# braino_schematic.net
KiCad netlist of a schematic drawn in EAGLE
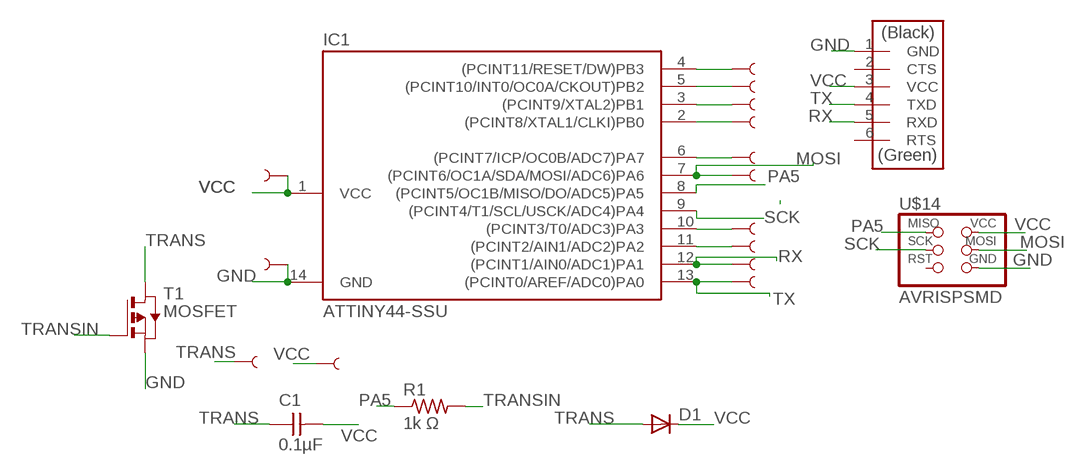
[diagram p0: schematic, sheet 1]

(export (version "E")
  (design (tool "Eeschema 10.0.6"))
  (components
    (comp (ref "C1")
      (value "0.1µF")
      (footprint "eagle-import:C1206FAB")
      (libsource (lib "eagle-import") (part "CAP-UNPOLARIZEDFAB"))
    )
    (comp (ref "D1")
      (value "DIODESOD123")
      (footprint "eagle-import:SOD123")
      (libsource (lib "eagle-import") (part "DIODESOD123"))
    )
    (comp (ref "IC1")
      (value "ATTINY44-SSU")
      (footprint "eagle-import:SOIC14")
      (libsource (lib "eagle-import") (part "ATTINY44-SSU"))
    )
    (comp (ref "R1")
      (value "1k Ω")
      (footprint "eagle-import:R1206FAB")
      (libsource (lib "eagle-import") (part "RES-US1206FAB"))
    )
    (comp (ref "T1")
      (value "MOSFET")
      (footprint "eagle-import:SOT-23")
      (libsource (lib "eagle-import") (part "PMOSFETSOT23"))
    )
    (comp (ref "U$1")
      (value "SEWTAP10")
      (footprint "eagle-import:PETAL-LONG-2-2SIDE")
      (libsource (lib "eagle-import") (part "SEWTAP10"))
    )
    (comp (ref "U$2")
      (value "SEWTAP10")
      (footprint "eagle-import:PETAL-LONG-2-2SIDE")
      (libsource (lib "eagle-import") (part "SEWTAP10"))
    )
    (comp (ref "U$3")
      (value "SEWTAP10")
      (footprint "eagle-import:PETAL-LONG-2-2SIDE")
      (libsource (lib "eagle-import") (part "SEWTAP10"))
    )
    (comp (ref "U$4")
      (value "SEWTAP10")
      (footprint "eagle-import:PETAL-LONG-2-2SIDE")
      (libsource (lib "eagle-import") (part "SEWTAP10"))
    )
    (comp (ref "U$5")
      (value "SEWTAP10")
      (footprint "eagle-import:PETAL-LONG-2-2SIDE")
      (libsource (lib "eagle-import") (part "SEWTAP10"))
    )
    (comp (ref "U$6")
      (value "SEWTAP10")
      (footprint "eagle-import:PETAL-LONG-2-2SIDE")
      (libsource (lib "eagle-import") (part "SEWTAP10"))
    )
    (comp (ref "U$9")
      (value "SEWTAP10")
      (footprint "eagle-import:PETAL-LONG-2-2SIDE")
      (libsource (lib "eagle-import") (part "SEWTAP10"))
    )
    (comp (ref "U$10")
      (value "SEWTAP10")
      (footprint "eagle-import:PETAL-LONG-2-2SIDE")
      (libsource (lib "eagle-import") (part "SEWTAP10"))
    )
    (comp (ref "U$11")
      (value "SEWTAP10")
      (footprint "eagle-import:PETAL-LONG-2-2SIDE")
      (libsource (lib "eagle-import") (part "SEWTAP10"))
    )
    (comp (ref "U$12")
      (value "SEWTAP10")
      (footprint "eagle-import:PETAL-LONG-2-2SIDE")
      (libsource (lib "eagle-import") (part "SEWTAP10"))
    )
    (comp (ref "U$13")
      (value "FTDI-SMD-HEADER")
      (footprint "eagle-import:1X06SMD")
      (libsource (lib "eagle-import") (part "FTDI-SMD-HEADER"))
    )
    (comp (ref "U$14")
      (value "AVRISPSMD")
      (footprint "eagle-import:2X03SMD")
      (libsource (lib "eagle-import") (part "AVRISPSMD"))
    )
    (comp (ref "U$15")
      (value "SEWTAP10")
      (footprint "eagle-import:PETAL-LONG-2-2SIDE")
      (libsource (lib "eagle-import") (part "SEWTAP10"))
    )
    (comp (ref "U$16")
      (value "SEWTAP10")
      (footprint "eagle-import:PETAL-LONG-2-2SIDE")
      (libsource (lib "eagle-import") (part "SEWTAP10"))
    )
    (comp (ref "U$17")
      (value "SEWTAP11")
      (footprint "eagle-import:PETAL-TINY")
      (libsource (lib "eagle-import") (part "SEWTAP11"))
    )
    (comp (ref "U$18")
      (value "SEWTAP11")
      (footprint "eagle-import:PETAL-TINY")
      (libsource (lib "eagle-import") (part "SEWTAP11"))
    )
  )
  (nets
    (net (code "1") (name "/GND") (class "Default")
      (node (ref "IC1") (pin "14") (pinfunction "GND_14") (pintype "power_in"))
      (node (ref "T1") (pin "2") (pinfunction "S_2") (pintype "passive"))
      (node (ref "U$13") (pin "1") (pinfunction "GND_1") (pintype "bidirectional"))
      (node (ref "U$14") (pin "6") (pinfunction "GND_6") (pintype "passive"))
      (node (ref "U$15") (pin "1") (pinfunction "1_1") (pintype "bidirectional"))
    )
    (net (code "2") (name "/MOSI") (class "Default")
      (node (ref "IC1") (pin "7") (pinfunction "(PCINT6/OC1A/SDA/MOSI/ADC6)PA6_7") (pintype "bidirectional"))
      (node (ref "U$14") (pin "4") (pinfunction "MOSI_4") (pintype "passive"))
      (node (ref "U$6") (pin "1") (pinfunction "1_1") (pintype "bidirectional"))
    )
    (net (code "3") (name "/PA5") (class "Default")
      (node (ref "IC1") (pin "8") (pinfunction "(PCINT5/OC1B/MISO/DO/ADC5)PA5_8") (pintype "bidirectional"))
      (node (ref "R1") (pin "1") (pinfunction "1_1") (pintype "passive"))
      (node (ref "U$14") (pin "1") (pinfunction "MISO_1") (pintype "passive"))
    )
    (net (code "4") (name "/RX") (class "Default")
      (node (ref "IC1") (pin "12") (pinfunction "(PCINT1/AIN0/ADC1)PA1_12") (pintype "bidirectional"))
      (node (ref "U$11") (pin "1") (pinfunction "1_1") (pintype "bidirectional"))
      (node (ref "U$13") (pin "5") (pinfunction "RXD_5") (pintype "bidirectional"))
    )
    (net (code "5") (name "/SCK") (class "Default")
      (node (ref "IC1") (pin "9") (pinfunction "(PCINT4/T1/SCL/USCK/ADC4)PA4_9") (pintype "bidirectional"))
      (node (ref "U$14") (pin "3") (pinfunction "SCK_3") (pintype "passive"))
    )
    (net (code "6") (name "/TRANS") (class "Default")
      (node (ref "C1") (pin "1") (pinfunction "1_1") (pintype "passive"))
      (node (ref "D1") (pin "ANODE") (pinfunction "A_ANODE") (pintype "passive"))
      (node (ref "T1") (pin "1") (pinfunction "D_1") (pintype "passive"))
      (node (ref "U$18") (pin "1") (pinfunction "1_1") (pintype "bidirectional"))
    )
    (net (code "7") (name "/TRANSIN") (class "Default")
      (node (ref "R1") (pin "2") (pinfunction "2_2") (pintype "passive"))
      (node (ref "T1") (pin "3") (pinfunction "G_3") (pintype "passive"))
    )
    (net (code "8") (name "/TX") (class "Default")
      (node (ref "IC1") (pin "13") (pinfunction "(PCINT0/AREF/ADC0)PA0_13") (pintype "bidirectional"))
      (node (ref "U$12") (pin "1") (pinfunction "1_1") (pintype "bidirectional"))
      (node (ref "U$13") (pin "4") (pinfunction "TXD_4") (pintype "bidirectional"))
    )
    (net (code "9") (name "/VCC") (class "Default")
      (node (ref "C1") (pin "2") (pinfunction "2_2") (pintype "passive"))
      (node (ref "D1") (pin "CATHODE") (pinfunction "C_CATHODE") (pintype "passive"))
      (node (ref "IC1") (pin "1") (pinfunction "VCC_1") (pintype "power_in"))
      (node (ref "U$13") (pin "3") (pinfunction "VCC_3") (pintype "bidirectional"))
      (node (ref "U$14") (pin "2") (pinfunction "VCC_2") (pintype "passive"))
      (node (ref "U$16") (pin "1") (pinfunction "1_1") (pintype "bidirectional"))
      (node (ref "U$17") (pin "1") (pinfunction "1_1") (pintype "bidirectional"))
    )
    (net (code "10") (name "Net-(IC1-(PCINT2{slash}AIN1{slash}ADC2)PA2)") (class "Default")
      (node (ref "IC1") (pin "11") (pinfunction "(PCINT2/AIN1/ADC2)PA2_11") (pintype "bidirectional"))
      (node (ref "U$10") (pin "1") (pinfunction "1_1") (pintype "bidirectional"))
    )
    (net (code "11") (name "Net-(IC1-(PCINT3{slash}T0{slash}ADC3)PA3)") (class "Default")
      (node (ref "IC1") (pin "10") (pinfunction "(PCINT3/T0/ADC3)PA3_10") (pintype "bidirectional"))
      (node (ref "U$9") (pin "1") (pinfunction "1_1") (pintype "bidirectional"))
    )
    (net (code "12") (name "Net-(IC1-(PCINT7{slash}ICP{slash}OC0B{slash}ADC7)PA7)") (class "Default")
      (node (ref "IC1") (pin "6") (pinfunction "(PCINT7/ICP/OC0B/ADC7)PA7_6") (pintype "bidirectional"))
      (node (ref "U$5") (pin "1") (pinfunction "1_1") (pintype "bidirectional"))
    )
    (net (code "13") (name "Net-(IC1-(PCINT8{slash}XTAL1{slash}CLKI)PB0)") (class "Default")
      (node (ref "IC1") (pin "2") (pinfunction "(PCINT8/XTAL1/CLKI)PB0_2") (pintype "bidirectional"))
      (node (ref "U$4") (pin "1") (pinfunction "1_1") (pintype "bidirectional"))
    )
    (net (code "14") (name "Net-(IC1-(PCINT9{slash}XTAL2)PB1)") (class "Default")
      (node (ref "IC1") (pin "3") (pinfunction "(PCINT9/XTAL2)PB1_3") (pintype "bidirectional"))
      (node (ref "U$3") (pin "1") (pinfunction "1_1") (pintype "bidirectional"))
    )
    (net (code "15") (name "Net-(IC1-(PCINT10{slash}INT0{slash}OC0A{slash}CKOUT)PB2)") (class "Default")
      (node (ref "IC1") (pin "5") (pinfunction "(PCINT10/INT0/OC0A/CKOUT)PB2_5") (pintype "bidirectional"))
      (node (ref "U$2") (pin "1") (pinfunction "1_1") (pintype "bidirectional"))
    )
    (net (code "16") (name "Net-(IC1-(PCINT11{slash}RESET{slash}DW)PB3)") (class "Default")
      (node (ref "IC1") (pin "4") (pinfunction "(PCINT11/RESET/DW)PB3_4") (pintype "bidirectional"))
      (node (ref "U$1") (pin "1") (pinfunction "1_1") (pintype "bidirectional"))
    )
    (net (code "17") (name "unconnected-(U$13-CTS-Pad2)") (class "Default")
      (node (ref "U$13") (pin "2") (pinfunction "CTS_2") (pintype "bidirectional"))
    )
    (net (code "18") (name "unconnected-(U$13-RTS-Pad6)") (class "Default")
      (node (ref "U$13") (pin "6") (pinfunction "RTS_6") (pintype "bidirectional"))
    )
    (net (code "19") (name "unconnected-(U$14-RST-Pad5)") (class "Default")
      (node (ref "U$14") (pin "5") (pinfunction "RST_5") (pintype "passive"))
    )
  )
)
